# FDCAN-ISO.net
KiCad netlist of a schematic drawn in Altium Designer
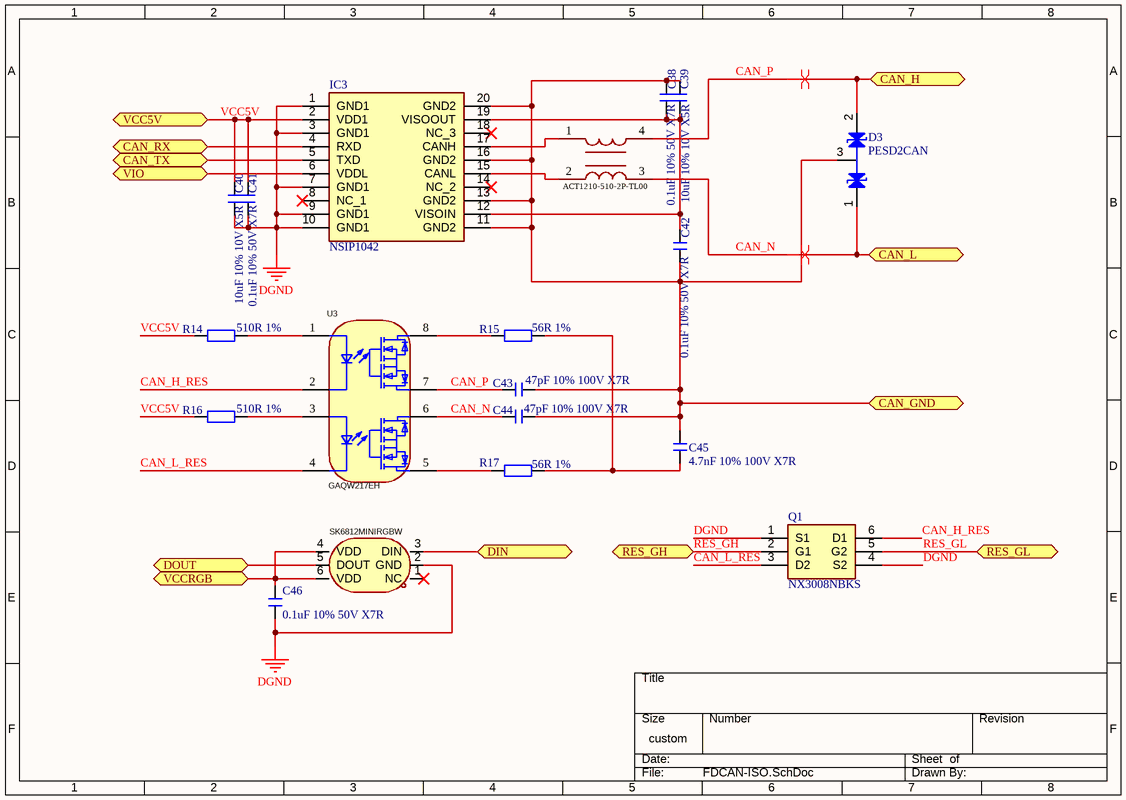
[diagram p0: FDCAN-ISO.SchDoc]

(export (version "E")
  (design (tool "Eeschema 10.0.6"))
  (components
    (comp (ref "C38")
      (value "0.1uF 10% 50V X7R")
      (footprint "C 0603_L")
      (description "贴片电容")
      (libsource (lib "0.1 - 电阻-电容-电感") (part "C"))
    )
    (comp (ref "C39")
      (value "10uF 10% 10V X5R")
      (footprint "C 0603_L")
      (description "贴片电容")
      (libsource (lib "0.1 - 电阻-电容-电感") (part "C"))
    )
    (comp (ref "C40")
      (value "10uF 10% 10V X5R")
      (footprint "C 0603_L")
      (description "贴片电容")
      (libsource (lib "0.1 - 电阻-电容-电感") (part "C"))
    )
    (comp (ref "C41")
      (value "0.1uF 10% 50V X7R")
      (footprint "C 0603_L")
      (description "贴片电容")
      (libsource (lib "0.1 - 电阻-电容-电感") (part "C"))
    )
    (comp (ref "C42")
      (value "0.1uF 10% 50V X7R")
      (footprint "C 0603_L")
      (description "贴片电容")
      (libsource (lib "0.1 - 电阻-电容-电感") (part "C"))
    )
    (comp (ref "C43")
      (value "47pF 10% 100V X7R")
      (footprint "C 0603_L")
      (description "贴片电容")
      (libsource (lib "0.1 - 电阻-电容-电感") (part "C"))
    )
    (comp (ref "C44")
      (value "47pF 10% 100V X7R")
      (footprint "C 0603_L")
      (description "贴片电容")
      (libsource (lib "0.1 - 电阻-电容-电感") (part "C"))
    )
    (comp (ref "C45")
      (value "4.7nF 10% 100V X7R")
      (footprint "C 0603_L")
      (description "贴片电容")
      (libsource (lib "0.1 - 电阻-电容-电感") (part "C"))
    )
    (comp (ref "C46")
      (value "0.1uF 10% 50V X7R")
      (footprint "C 0603_L")
      (description "贴片电容")
      (libsource (lib "0.1 - 电阻-电容-电感") (part "C"))
    )
    (comp (ref "D3")
      (value "PESD2CAN")
      (footprint "SOT23-3L")
      (libsource (lib "mx_pcb_library") (part "PESD2CAN"))
    )
    (comp (ref "IC3")
      (value "NSIP1042")
      (footprint "SOP20")
      (description "Integrated Circuit")
      (libsource (lib "mx_pcb_library") (part "NSIP1042"))
    )
    (comp (ref "L4")
      (value "ACT1210-510-2P-TL00")
      (footprint "SMD_4P-L3.2-W2.5")
      (fields (field (name "MANUFACTURER") "TDK") (field (name "MANUFACTURER PART") "ACT45B-510-2P-TL003"))
      (libsource (lib "mx_pcb_library") (part "ACT1210-510-2P-TL00"))
    )
    (comp (ref "LED2")
      (value "SK6812MINIRGBW")
      (footprint "LED-ARRAY-SMD_6P-L3.7-W3.5")
      (fields
        (field (name "MANUFACTURER") "欧思科光电")
        (field (name "MANUFACTURER PART") "SK6812MINIRGBW-BW-P6-A")
      )
      (libsource (lib "mx_pcb_library") (part "SK6812MINIRGBW-BW-P6-A"))
    )
    (comp (ref "Q1")
      (value "NX3008NBKS")
      (footprint "SOT-363")
      (description "MOSFET (N-Channel)")
      (fields
        (field (name "MANUFACTURER_PART_NUMBER") "NX3008NBKS,115")
        (field (name "MOUSER PART NUMBER") "771-NX3008NBKS,115")
      )
      (libsource (lib "mx_pcb_library") (part "NX3008NBKS"))
    )
    (comp (ref "R14")
      (value "510R 1%")
      (footprint "R 0603_L")
      (description "贴片电阻")
      (libsource (lib "0.1 - 电阻-电容-电感") (part "R"))
    )
    (comp (ref "R15")
      (value "56R 1%")
      (footprint "R 0603_L")
      (description "贴片电阻")
      (libsource (lib "0.1 - 电阻-电容-电感") (part "R"))
    )
    (comp (ref "R16")
      (value "510R 1%")
      (footprint "R 0603_L")
      (description "贴片电阻")
      (libsource (lib "0.1 - 电阻-电容-电感") (part "R"))
    )
    (comp (ref "R17")
      (value "56R 1%")
      (footprint "R 0603_L")
      (description "贴片电阻")
      (libsource (lib "0.1 - 电阻-电容-电感") (part "R"))
    )
    (comp (ref "U3")
      (value "GAQW217EH")
      (footprint "SMD-8_L9.9-W6.4-P2.54-LS10.0-BR")
      (fields (field (name "MANUFACTURER") "SUPSiC(国晶微半导体)"))
      (libsource (lib "mx_pcb_library") (part "GAQW217EH"))
    )
  )
  (nets
    (net (code "1") (name "/CAN_GND") (class "Default")
      (node (ref "C38") (pin "2") (pinfunction "2_2") (pintype "passive"))
      (node (ref "C39") (pin "1") (pinfunction "1_1") (pintype "passive"))
      (node (ref "C42") (pin "1") (pinfunction "1_1") (pintype "passive"))
      (node (ref "C43") (pin "2") (pinfunction "2_2") (pintype "passive"))
      (node (ref "C44") (pin "1") (pinfunction "1_1") (pintype "passive"))
      (node (ref "C45") (pin "1") (pinfunction "1_1") (pintype "passive"))
      (node (ref "D3") (pin "3") (pinfunction "3_3") (pintype "passive"))
      (node (ref "IC3") (pin "11") (pinfunction "GND2_11") (pintype "passive"))
      (node (ref "IC3") (pin "13") (pinfunction "GND2_13") (pintype "passive"))
      (node (ref "IC3") (pin "16") (pinfunction "GND2_16") (pintype "passive"))
      (node (ref "IC3") (pin "20") (pinfunction "GND2_20") (pintype "passive"))
    )
    (net (code "2") (name "/CAN_H_RES") (class "Default")
      (node (ref "Q1") (pin "6") (pinfunction "D1_6") (pintype "passive"))
      (node (ref "U3") (pin "2") (pinfunction "2_2") (pintype "passive"))
    )
    (net (code "3") (name "/CAN_L_RES") (class "Default")
      (node (ref "Q1") (pin "3") (pinfunction "D2_3") (pintype "passive"))
      (node (ref "U3") (pin "4") (pinfunction "4_4") (pintype "passive"))
    )
    (net (code "4") (name "/CAN_N") (class "Default")
      (node (ref "C44") (pin "2") (pinfunction "2_2") (pintype "passive"))
      (node (ref "D3") (pin "1") (pinfunction "1_1") (pintype "passive"))
      (node (ref "L4") (pin "3") (pinfunction "3_3") (pintype "passive"))
      (node (ref "U3") (pin "6") (pinfunction "6_6") (pintype "passive"))
    )
    (net (code "5") (name "/CAN_P") (class "Default")
      (node (ref "C43") (pin "1") (pinfunction "1_1") (pintype "passive"))
      (node (ref "D3") (pin "2") (pinfunction "2_2") (pintype "passive"))
      (node (ref "L4") (pin "4") (pinfunction "4_4") (pintype "passive"))
      (node (ref "U3") (pin "7") (pinfunction "7_7") (pintype "passive"))
    )
    (net (code "6") (name "/CAN_RX") (class "Default")
      (node (ref "IC3") (pin "4") (pinfunction "RXD_4") (pintype "passive"))
    )
    (net (code "7") (name "/CAN_TX") (class "Default")
      (node (ref "IC3") (pin "5") (pinfunction "TXD_5") (pintype "passive"))
    )
    (net (code "8") (name "/DIN") (class "Default")
      (node (ref "LED2") (pin "3") (pinfunction "DIN_3") (pintype "passive"))
    )
    (net (code "9") (name "/DOUT") (class "Default")
      (node (ref "LED2") (pin "5") (pinfunction "DOUT_5") (pintype "passive"))
    )
    (net (code "10") (name "/RES_GH") (class "Default")
      (node (ref "Q1") (pin "2") (pinfunction "G1_2") (pintype "passive"))
    )
    (net (code "11") (name "/RES_GL") (class "Default")
      (node (ref "Q1") (pin "5") (pinfunction "G2_5") (pintype "passive"))
    )
    (net (code "12") (name "/VCC5V") (class "Default")
      (node (ref "C40") (pin "1") (pinfunction "1_1") (pintype "passive"))
      (node (ref "C41") (pin "2") (pinfunction "2_2") (pintype "passive"))
      (node (ref "IC3") (pin "2") (pinfunction "VDD1_2") (pintype "passive"))
      (node (ref "R14") (pin "2") (pinfunction "2_2") (pintype "passive"))
      (node (ref "R16") (pin "2") (pinfunction "2_2") (pintype "passive"))
    )
    (net (code "13") (name "/VCCRGB") (class "Default")
      (node (ref "C46") (pin "2") (pinfunction "2_2") (pintype "passive"))
      (node (ref "LED2") (pin "4") (pinfunction "VDD_4") (pintype "passive"))
      (node (ref "LED2") (pin "6") (pinfunction "VDD_6") (pintype "passive"))
    )
    (net (code "14") (name "/VIO") (class "Default")
      (node (ref "IC3") (pin "6") (pinfunction "VDDL_6") (pintype "passive"))
    )
    (net (code "15") (name "DGND") (class "Default")
      (node (ref "C40") (pin "2") (pinfunction "2_2") (pintype "passive"))
      (node (ref "C41") (pin "1") (pinfunction "1_1") (pintype "passive"))
      (node (ref "C46") (pin "1") (pinfunction "1_1") (pintype "passive"))
      (node (ref "IC3") (pin "1") (pinfunction "GND1_1") (pintype "passive"))
      (node (ref "IC3") (pin "10") (pinfunction "GND1_10") (pintype "passive"))
      (node (ref "IC3") (pin "3") (pinfunction "GND1_3") (pintype "passive"))
      (node (ref "IC3") (pin "7") (pinfunction "GND1_7") (pintype "passive"))
      (node (ref "IC3") (pin "9") (pinfunction "GND1_9") (pintype "passive"))
      (node (ref "LED2") (pin "2") (pinfunction "GND_2") (pintype "passive"))
      (node (ref "Q1") (pin "1") (pinfunction "S1_1") (pintype "passive"))
      (node (ref "Q1") (pin "4") (pinfunction "S2_4") (pintype "passive"))
    )
    (net (code "16") (name "Net-(C45-Pad2)") (class "Default")
      (node (ref "C45") (pin "2") (pinfunction "2_2") (pintype "passive"))
      (node (ref "R15") (pin "1") (pinfunction "1_1") (pintype "passive"))
      (node (ref "R17") (pin "2") (pinfunction "2_2") (pintype "passive"))
    )
    (net (code "17") (name "Net-(IC3-CANH)") (class "Default")
      (node (ref "IC3") (pin "17") (pinfunction "CANH_17") (pintype "passive"))
      (node (ref "L4") (pin "1") (pinfunction "1_1") (pintype "passive"))
    )
    (net (code "18") (name "Net-(IC3-CANL)") (class "Default")
      (node (ref "IC3") (pin "15") (pinfunction "CANL_15") (pintype "passive"))
      (node (ref "L4") (pin "2") (pinfunction "2_2") (pintype "passive"))
    )
    (net (code "19") (name "Net-(IC3-VISOIN)") (class "Default")
      (node (ref "C38") (pin "1") (pinfunction "1_1") (pintype "passive"))
      (node (ref "C39") (pin "2") (pinfunction "2_2") (pintype "passive"))
      (node (ref "C42") (pin "2") (pinfunction "2_2") (pintype "passive"))
      (node (ref "IC3") (pin "12") (pinfunction "VISOIN_12") (pintype "passive"))
      (node (ref "IC3") (pin "19") (pinfunction "VISOOUT_19") (pintype "passive"))
    )
    (net (code "20") (name "Net-(R14-Pad1)") (class "Default")
      (node (ref "R14") (pin "1") (pinfunction "1_1") (pintype "passive"))
      (node (ref "U3") (pin "1") (pinfunction "1_1") (pintype "passive"))
    )
    (net (code "21") (name "Net-(R15-Pad2)") (class "Default")
      (node (ref "R15") (pin "2") (pinfunction "2_2") (pintype "passive"))
      (node (ref "U3") (pin "8") (pinfunction "8_8") (pintype "passive"))
    )
    (net (code "22") (name "Net-(R16-Pad1)") (class "Default")
      (node (ref "R16") (pin "1") (pinfunction "1_1") (pintype "passive"))
      (node (ref "U3") (pin "3") (pinfunction "3_3") (pintype "passive"))
    )
    (net (code "23") (name "Net-(R17-Pad1)") (class "Default")
      (node (ref "R17") (pin "1") (pinfunction "1_1") (pintype "passive"))
      (node (ref "U3") (pin "5") (pinfunction "5_5") (pintype "passive"))
    )
    (net (code "24") (name "unconnected-(IC3-NC_1-Pad8)") (class "Default")
      (node (ref "IC3") (pin "8") (pinfunction "NC_1_8") (pintype "passive+no_connect"))
    )
    (net (code "25") (name "unconnected-(IC3-NC_2-Pad14)") (class "Default")
      (node (ref "IC3") (pin "14") (pinfunction "NC_2_14") (pintype "passive+no_connect"))
    )
    (net (code "26") (name "unconnected-(IC3-NC_3-Pad18)") (class "Default")
      (node (ref "IC3") (pin "18") (pinfunction "NC_3_18") (pintype "passive+no_connect"))
    )
    (net (code "27") (name "unconnected-(LED2-NC-Pad1)") (class "Default")
      (node (ref "LED2") (pin "1") (pinfunction "NC_1") (pintype "passive+no_connect"))
    )
  )
)
